# control_block.net
KiCad netlist of a schematic drawn in Altium Designer
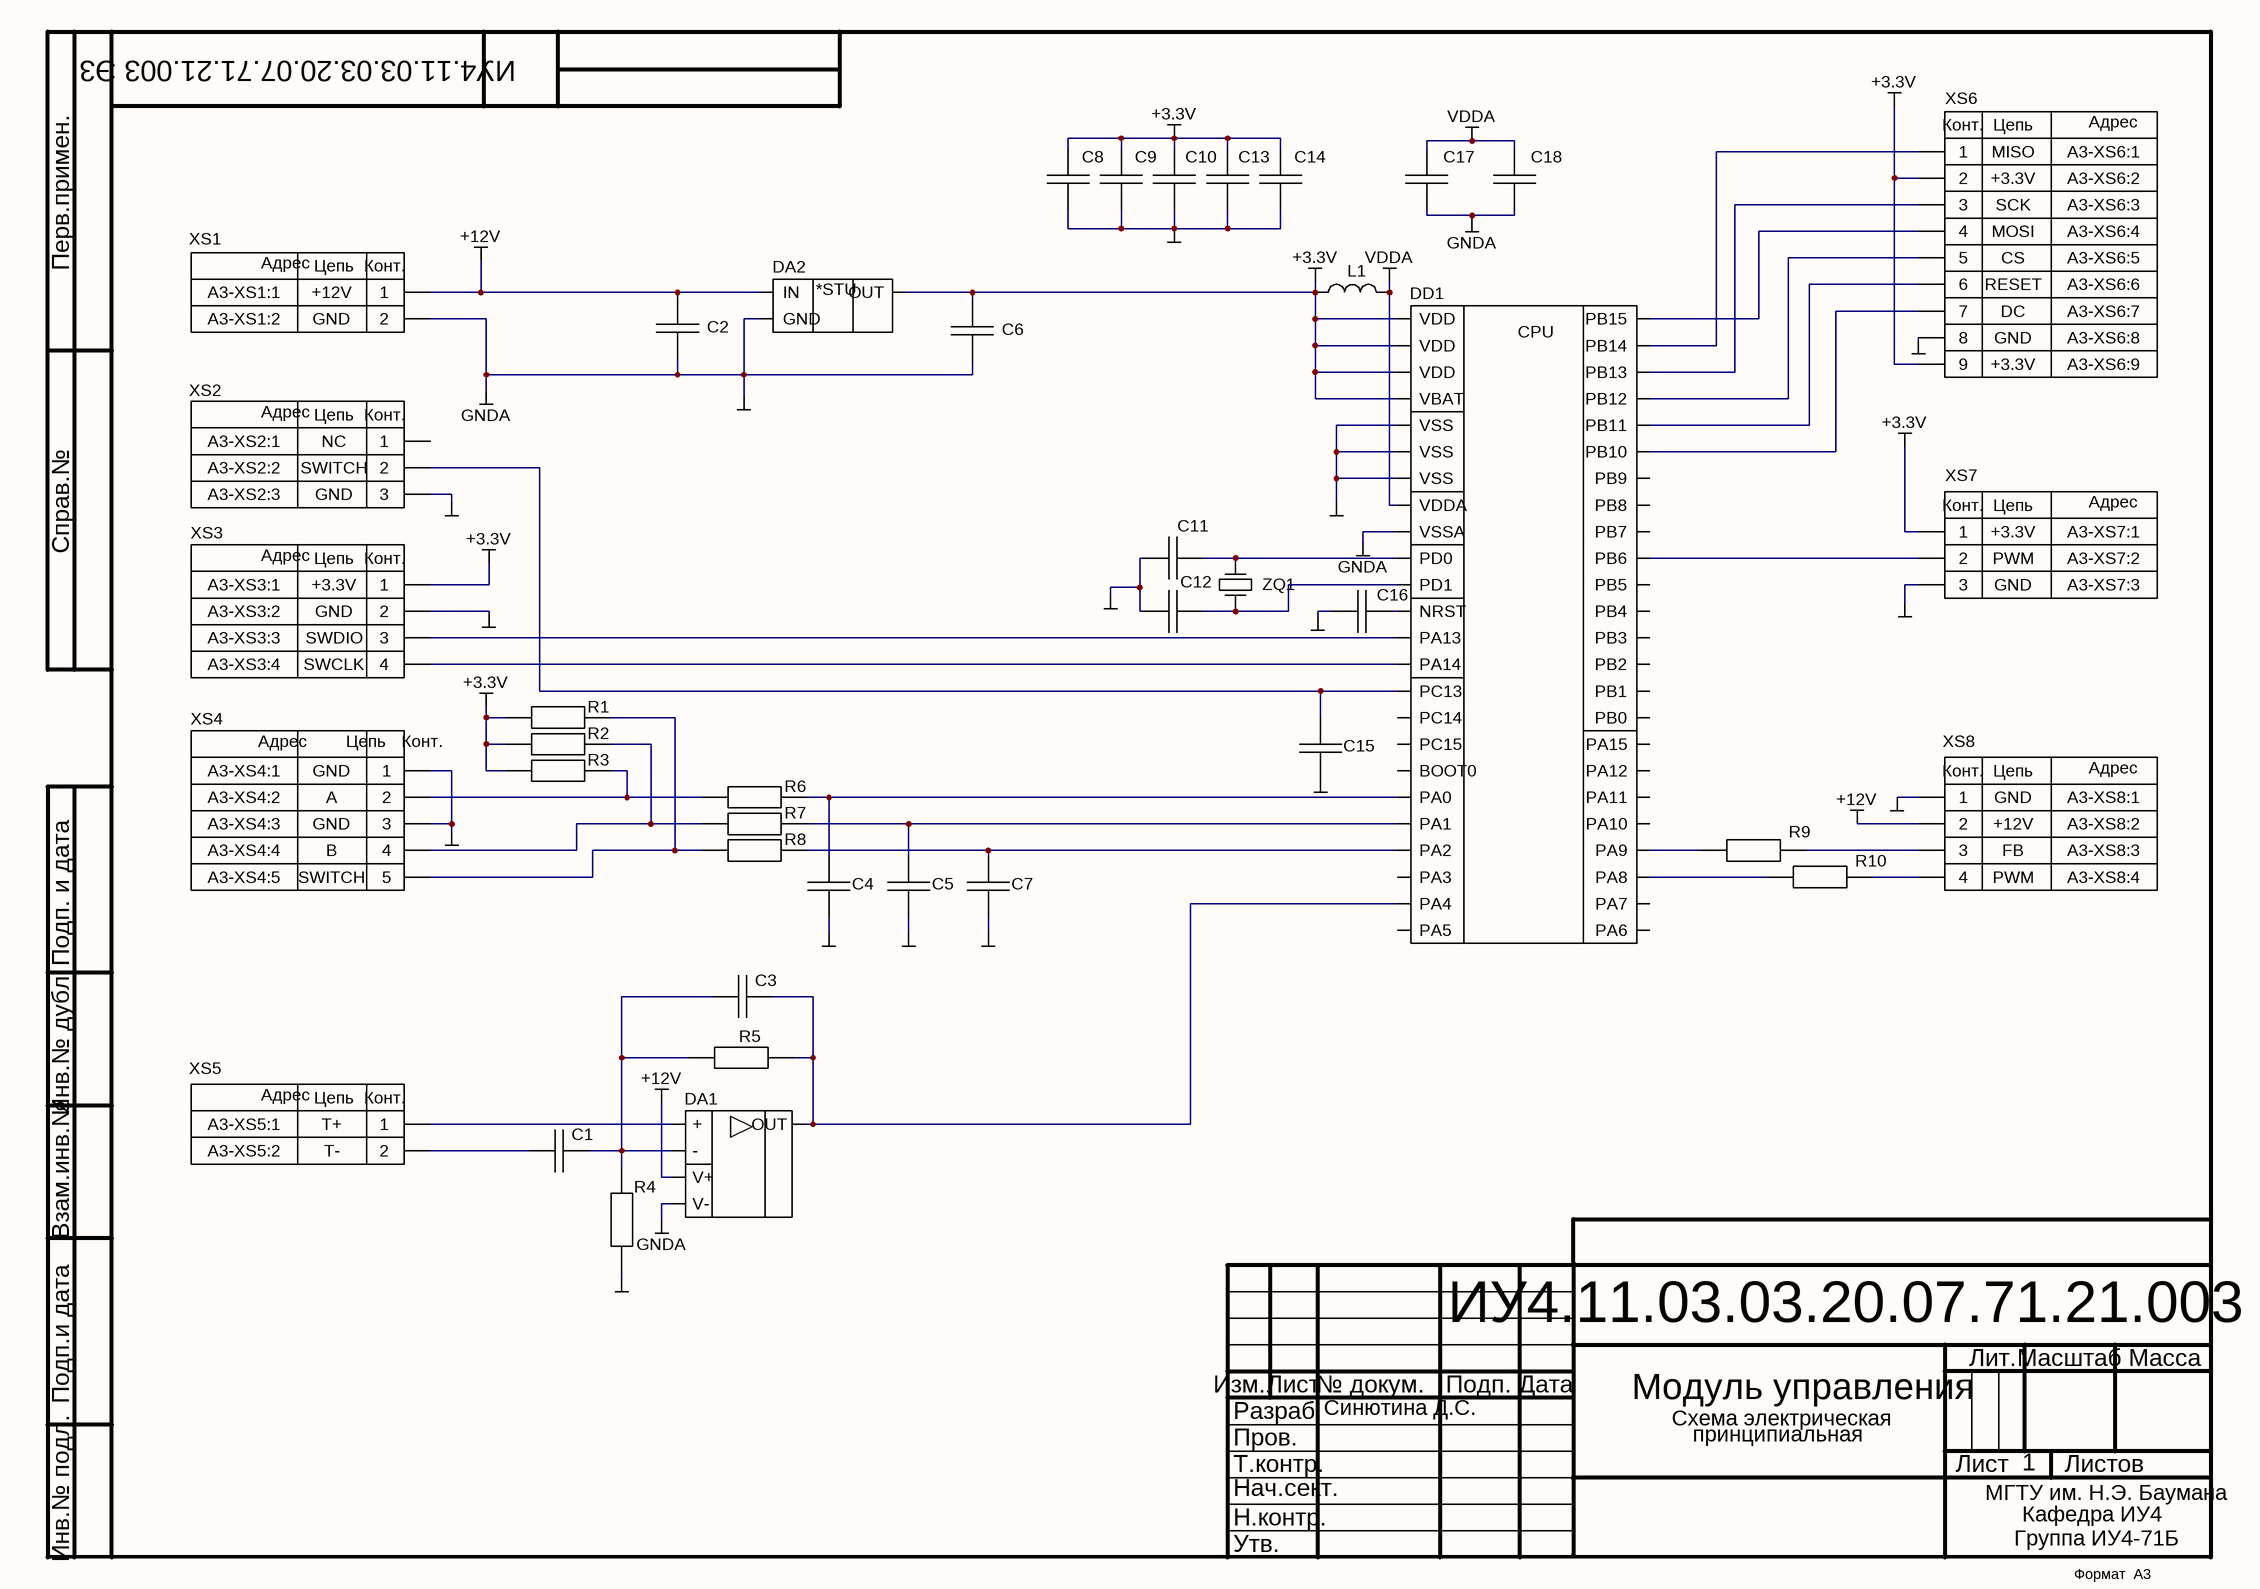
[diagram p0: control_block.SchDoc]

(export (version "E")
  (design (tool "Eeschema 10.0.6"))
  (components
    (comp (ref "C1") (value "100 нФ") (footprint "CAP: 0603") (libsource (lib "elems") (part "C_const")))
    (comp (ref "C2") (value "330 нФ") (footprint "CAP: 0603") (libsource (lib "elems") (part "C_const")))
    (comp (ref "C3") (value "100 нФ") (footprint "CAP: 0603") (libsource (lib "elems") (part "C_const")))
    (comp (ref "C4") (value "100 нФ") (footprint "CAP: 0603") (libsource (lib "elems") (part "C_const")))
    (comp (ref "C5") (value "100 нФ") (footprint "CAP: 0603") (libsource (lib "elems") (part "C_const")))
    (comp (ref "C6") (value "100 нФ") (footprint "CAP: 0603") (libsource (lib "elems") (part "C_const")))
    (comp (ref "C7") (value "100 нФ") (footprint "CAP: 0603") (libsource (lib "elems") (part "C_const")))
    (comp (ref "C8") (value "100 нФ") (footprint "CAP: 0603") (libsource (lib "elems") (part "C_const")))
    (comp (ref "C9") (value "100 нФ") (footprint "CAP: 0603") (libsource (lib "elems") (part "C_const")))
    (comp (ref "C10") (value "100 нФ") (footprint "CAP: 0603") (libsource (lib "elems") (part "C_const")))
    (comp (ref "C11") (value "22 pF") (footprint "CAP: 0603") (libsource (lib "elems") (part "C_const")))
    (comp (ref "C12") (value "22 pF") (footprint "CAP: 0603") (libsource (lib "elems") (part "C_const")))
    (comp (ref "C13") (value "100 нФ") (footprint "CAP: 0603") (libsource (lib "elems") (part "C_const")))
    (comp (ref "C14") (value "4.7 мкФ") (footprint "CAP: 0603") (libsource (lib "elems") (part "C_const")))
    (comp (ref "C15") (value "100 нФ") (footprint "CAP: 0603") (libsource (lib "") (part "C_const_2")))
    (comp (ref "C16") (value "100 нФ") (footprint "CAP: 0603") (libsource (lib "") (part "C_const_1")))
    (comp (ref "C17") (value "10 нФ") (footprint "CAP: 0603") (libsource (lib "elems") (part "C_const")))
    (comp (ref "C18") (value "1 мкФ") (footprint "CAP: 0603") (libsource (lib "elems") (part "C_const")))
    (comp (ref "DA1")
      (value "TS321ILT")
      (footprint "SOT23-5")
      (libsource (lib "elems") (part "single_channel_op_amp"))
    )
    (comp (ref "DA2") (value "78xx") (footprint "SOT89") (libsource (lib "elems") (part "78xx")))
    (comp (ref "DD1")
      (value "STM32F103C8T6")
      (footprint "48-LQFP")
      (libsource (lib "elems") (part "STM32F103C8T6"))
    )
    (comp (ref "L1") (value "10 мкГн") (footprint "IND: 0805") (libsource (lib "elems") (part "L")))
    (comp (ref "R1") (value "10кОм") (footprint "RES: 0603") (libsource (lib "elems") (part "Res")))
    (comp (ref "R2") (value "10кОм") (footprint "RES: 0603") (libsource (lib "elems") (part "Res")))
    (comp (ref "R3") (value "10кОм") (footprint "RES: 0603") (libsource (lib "elems") (part "Res")))
    (comp (ref "R4") (value "1 кОм") (footprint "RES: 1206") (libsource (lib "elems") (part "Res")))
    (comp (ref "R5") (value "47 кОм") (footprint "RES: 1206") (libsource (lib "elems") (part "Res")))
    (comp (ref "R6") (value "10кОм") (footprint "RES: 0603") (libsource (lib "elems") (part "Res")))
    (comp (ref "R7") (value "10кОм") (footprint "RES: 0603") (libsource (lib "elems") (part "Res")))
    (comp (ref "R8") (value "10кОм") (footprint "RES: 0603") (libsource (lib "elems") (part "Res")))
    (comp (ref "R9") (value "220 Ом") (footprint "RES: 1206") (libsource (lib "elems") (part "Res")))
    (comp (ref "R10") (value "220 Ом") (footprint "RES: 1206") (libsource (lib "elems") (part "Res")))
    (comp (ref "XS1")
      (value "X2")
      (footprint "CON: WF-02")
      (fields
        (field (name "CIRCUIT2") "GND")
        (field (name "CIRCUIT1") "+12V")
        (field (name "=ADDRESS2") "A3-XS1:2")
        (field (name "=ADDRESS1") "A3-XS1:1")
      )
      (libsource (lib "elems") (part "X2"))
    )
    (comp (ref "XS2")
      (value "X3")
      (footprint "CON: WF-03")
      (fields
        (field (name "CIRCUIT1") "NC")
        (field (name "CIRCUIT2") "SWITCH")
        (field (name "CIRCUIT3") "GND")
        (field (name "=ADDRESS1") "A3-XS2:1")
        (field (name "=ADDRESS2") "A3-XS2:2")
        (field (name "=ADDRESS3") "A3-XS2:3")
      )
      (libsource (lib "elems") (part "X3"))
    )
    (comp (ref "XS3")
      (value "X4")
      (footprint "CON: WF-04")
      (fields
        (field (name "CIRCUIT2") "GND")
        (field (name "CIRCUIT3") "SWDIO")
        (field (name "CIRCUIT1") "+3.3V")
        (field (name "CIRCUIT4") "SWCLK")
        (field (name "=ADDRESS4") "A3-XS3:4")
        (field (name "=ADDRESS3") "A3-XS3:3")
        (field (name "=ADDRESS2") "A3-XS3:2")
        (field (name "=ADDRESS1") "A3-XS3:1")
      )
      (libsource (lib "elems") (part "X4"))
    )
    (comp (ref "XS4")
      (value "X5")
      (footprint "CON: CWF-5")
      (fields
        (field (name "CIRTUIT5") "SWITCH")
        (field (name "CIRCUIT4") "B")
        (field (name "CIRCUIT3") "GND")
        (field (name "CIRCUIT2") "A")
        (field (name "CIRCUIT1") "GND")
        (field (name "=ADDRESS5") "A3-XS4:5")
        (field (name "=ADDRESS4") "A3-XS4:4")
        (field (name "=ADDRESS3") "A3-XS4:3")
        (field (name "=ADDRESS2") "A3-XS4:2")
        (field (name "=ADDRESS1") "A3-XS4:1")
      )
      (libsource (lib "elems") (part "X5"))
    )
    (comp (ref "XS5")
      (value "X2")
      (footprint "CON: WF-02")
      (fields
        (field (name "CIRCUIT2") "T-")
        (field (name "CIRCUIT1") "T+")
        (field (name "=ADDRESS2") "A3-XS5:2")
        (field (name "=ADDRESS1") "A3-XS5:1")
      )
      (libsource (lib "") (part "X2_1"))
    )
    (comp (ref "XS6")
      (value "X9")
      (footprint "CON: IDC-10MS")
      (fields
        (field (name "CIRCTUIT9") "+3.3V")
        (field (name "CIRCTUIT8") "GND")
        (field (name "CIRCTUIT7") "DC")
        (field (name "CIRCTUIT6") "RESET")
        (field (name "CIRCTUIT5") "CS")
        (field (name "CIRCTUIT4") "MOSI")
        (field (name "CIRCTUIT3") "SCK")
        (field (name "CIRCTUIT2") "+3.3V")
        (field (name "CIRCTUIT1") "MISO")
        (field (name "=ADDRESS9") "A3-XS6:9")
        (field (name "=ADDRESS8") "A3-XS6:8")
        (field (name "=ADDRESS7") "A3-XS6:7")
        (field (name "=ADDRESS5") "A3-XS6:5")
        (field (name "=ADDRESS6") "A3-XS6:6")
        (field (name "=ADDRESS4") "A3-XS6:4")
        (field (name "=ADDRESS3") "A3-XS6:3")
        (field (name "=ADDRESS2") "A3-XS6:2")
        (field (name "=ADDRESS1") "A3-XS6:1")
      )
      (libsource (lib "elems") (part "X9"))
    )
    (comp (ref "XS7")
      (value "X3")
      (footprint "CON: WF-03")
      (fields
        (field (name "CIRCUIT1") "+3.3V")
        (field (name "CIRCUIT2") "PWM")
        (field (name "CIRCUIT3") "GND")
        (field (name "=ADDRESS1") "A3-XS7:1")
        (field (name "=ADDRESS2") "A3-XS7:2")
        (field (name "=ADDRESS3") "A3-XS7:3")
      )
      (libsource (lib "elems") (part "X3"))
    )
    (comp (ref "XS8")
      (value "X4")
      (footprint "CON: WF-04")
      (fields
        (field (name "CIRCUIT2") "+12V")
        (field (name "CIRCUIT3") "FB")
        (field (name "CIRCUIT1") "GND")
        (field (name "CIRCUIT4") "PWM")
        (field (name "=ADDRESS4") "A3-XS8:4")
        (field (name "=ADDRESS3") "A3-XS8:3")
        (field (name "=ADDRESS2") "A3-XS8:2")
        (field (name "=ADDRESS1") "A3-XS8:1")
      )
      (libsource (lib "elems") (part "X4"))
    )
    (comp (ref "ZQ1") (value "AT-41CD2-8MHz") (footprint "AT-41CD2") (libsource (lib "elems") (part "ZQ")))
  )
  (nets
    (net (code "1") (name "+3.3V") (class "Default")
      (node (ref "C10") (pin "2") (pinfunction "2_2") (pintype "passive"))
      (node (ref "C13") (pin "2") (pinfunction "2_2") (pintype "passive"))
      (node (ref "C14") (pin "2") (pinfunction "2_2") (pintype "passive"))
      (node (ref "C6") (pin "2") (pinfunction "2_2") (pintype "passive"))
      (node (ref "C8") (pin "2") (pinfunction "2_2") (pintype "passive"))
      (node (ref "C9") (pin "2") (pinfunction "2_2") (pintype "passive"))
      (node (ref "DA2") (pin "2") (pinfunction "OUT_2") (pintype "passive"))
      (node (ref "DD1") (pin "1") (pinfunction "VBAT_1") (pintype "passive"))
      (node (ref "DD1") (pin "24") (pinfunction "VDD_24") (pintype "passive"))
      (node (ref "DD1") (pin "36") (pinfunction "VDD_36") (pintype "passive"))
      (node (ref "DD1") (pin "48") (pinfunction "VDD_48") (pintype "passive"))
      (node (ref "L1") (pin "1") (pinfunction "1_1") (pintype "passive"))
      (node (ref "R1") (pin "2") (pinfunction "6_2") (pintype "passive"))
      (node (ref "R2") (pin "2") (pinfunction "6_2") (pintype "passive"))
      (node (ref "R3") (pin "2") (pinfunction "6_2") (pintype "passive"))
      (node (ref "XS3") (pin "1") (pinfunction "1_1") (pintype "passive"))
      (node (ref "XS6") (pin "2") (pinfunction "2_2") (pintype "passive"))
      (node (ref "XS6") (pin "9") (pinfunction "9_9") (pintype "passive"))
      (node (ref "XS7") (pin "1") (pinfunction "1_1") (pintype "passive"))
    )
    (net (code "2") (name "+12V") (class "Default")
      (node (ref "C2") (pin "2") (pinfunction "2_2") (pintype "passive"))
      (node (ref "DA1") (pin "5") (pinfunction "V+_5") (pintype "passive"))
      (node (ref "DA2") (pin "1") (pinfunction "IN_1") (pintype "passive"))
      (node (ref "XS1") (pin "1") (pinfunction "1_1") (pintype "passive"))
      (node (ref "XS8") (pin "2") (pinfunction "2_2") (pintype "passive"))
    )
    (net (code "3") (name "GND") (class "Default")
      (node (ref "C10") (pin "1") (pinfunction "1_1") (pintype "passive"))
      (node (ref "C11") (pin "1") (pinfunction "1_1") (pintype "passive"))
      (node (ref "C12") (pin "1") (pinfunction "1_1") (pintype "passive"))
      (node (ref "C13") (pin "1") (pinfunction "1_1") (pintype "passive"))
      (node (ref "C14") (pin "1") (pinfunction "1_1") (pintype "passive"))
      (node (ref "C15") (pin "1") (pinfunction "1_1") (pintype "passive"))
      (node (ref "C16") (pin "1") (pinfunction "1_1") (pintype "passive"))
      (node (ref "C17") (pin "1") (pinfunction "1_1") (pintype "passive"))
      (node (ref "C18") (pin "1") (pinfunction "1_1") (pintype "passive"))
      (node (ref "C2") (pin "1") (pinfunction "1_1") (pintype "passive"))
      (node (ref "C4") (pin "1") (pinfunction "1_1") (pintype "passive"))
      (node (ref "C5") (pin "1") (pinfunction "1_1") (pintype "passive"))
      (node (ref "C6") (pin "1") (pinfunction "1_1") (pintype "passive"))
      (node (ref "C7") (pin "1") (pinfunction "1_1") (pintype "passive"))
      (node (ref "C8") (pin "1") (pinfunction "1_1") (pintype "passive"))
      (node (ref "C9") (pin "1") (pinfunction "1_1") (pintype "passive"))
      (node (ref "DA1") (pin "2") (pinfunction "V-_2") (pintype "passive"))
      (node (ref "DA2") (pin "3") (pinfunction "GND_3") (pintype "passive"))
      (node (ref "DD1") (pin "23") (pinfunction "VSS_23") (pintype "passive"))
      (node (ref "DD1") (pin "35") (pinfunction "VSS_35") (pintype "passive"))
      (node (ref "DD1") (pin "47") (pinfunction "VSS_47") (pintype "passive"))
      (node (ref "DD1") (pin "8") (pinfunction "VSSA_8") (pintype "passive"))
      (node (ref "R4") (pin "2") (pinfunction "6_2") (pintype "passive"))
      (node (ref "XS1") (pin "2") (pinfunction "2_2") (pintype "passive"))
      (node (ref "XS2") (pin "3") (pinfunction "3_3") (pintype "passive"))
      (node (ref "XS3") (pin "2") (pinfunction "2_2") (pintype "passive"))
      (node (ref "XS4") (pin "1") (pinfunction "1_1") (pintype "passive"))
      (node (ref "XS4") (pin "3") (pinfunction "3_3") (pintype "passive"))
      (node (ref "XS6") (pin "8") (pinfunction "8_8") (pintype "passive"))
      (node (ref "XS7") (pin "3") (pinfunction "3_3") (pintype "passive"))
      (node (ref "XS8") (pin "1") (pinfunction "1_1") (pintype "passive"))
    )
    (net (code "4") (name "Net-(C1-Pad1)") (class "Default")
      (node (ref "C1") (pin "1") (pinfunction "1_1") (pintype "passive"))
      (node (ref "XS5") (pin "2") (pinfunction "2_2") (pintype "passive"))
    )
    (net (code "5") (name "Net-(DA1-+)") (class "Default")
      (node (ref "DA1") (pin "1") (pinfunction "+_1") (pintype "passive"))
      (node (ref "XS5") (pin "1") (pinfunction "1_1") (pintype "passive"))
    )
    (net (code "6") (name "Net-(DA1--)") (class "Default")
      (node (ref "C1") (pin "2") (pinfunction "2_2") (pintype "passive"))
      (node (ref "C3") (pin "1") (pinfunction "1_1") (pintype "passive"))
      (node (ref "DA1") (pin "3") (pinfunction "-_3") (pintype "passive"))
      (node (ref "R4") (pin "1") (pinfunction "1_1") (pintype "passive"))
      (node (ref "R5") (pin "1") (pinfunction "1_1") (pintype "passive"))
    )
    (net (code "7") (name "Net-(DA1-OUT)") (class "Default")
      (node (ref "C3") (pin "2") (pinfunction "2_2") (pintype "passive"))
      (node (ref "DA1") (pin "4") (pinfunction "OUT_4") (pintype "passive"))
      (node (ref "DD1") (pin "14") (pinfunction "PA4_14") (pintype "passive"))
      (node (ref "R5") (pin "2") (pinfunction "6_2") (pintype "passive"))
    )
    (net (code "8") (name "Net-(DD1-NRST)") (class "Default")
      (node (ref "C16") (pin "2") (pinfunction "2_2") (pintype "passive"))
      (node (ref "DD1") (pin "7") (pinfunction "NRST_7") (pintype "passive"))
    )
    (net (code "9") (name "Net-(DD1-PA0)") (class "Default")
      (node (ref "C4") (pin "2") (pinfunction "2_2") (pintype "passive"))
      (node (ref "DD1") (pin "10") (pinfunction "PA0_10") (pintype "passive"))
      (node (ref "R6") (pin "2") (pinfunction "6_2") (pintype "passive"))
    )
    (net (code "10") (name "Net-(DD1-PA1)") (class "Default")
      (node (ref "C5") (pin "2") (pinfunction "2_2") (pintype "passive"))
      (node (ref "DD1") (pin "11") (pinfunction "PA1_11") (pintype "passive"))
      (node (ref "R7") (pin "2") (pinfunction "6_2") (pintype "passive"))
    )
    (net (code "11") (name "Net-(DD1-PA2)") (class "Default")
      (node (ref "C7") (pin "2") (pinfunction "2_2") (pintype "passive"))
      (node (ref "DD1") (pin "12") (pinfunction "PA2_12") (pintype "passive"))
      (node (ref "R8") (pin "2") (pinfunction "6_2") (pintype "passive"))
    )
    (net (code "12") (name "Net-(DD1-PA8)") (class "Default")
      (node (ref "DD1") (pin "29") (pinfunction "PA8_29") (pintype "passive"))
      (node (ref "R10") (pin "1") (pinfunction "1_1") (pintype "passive"))
    )
    (net (code "13") (name "Net-(DD1-PA9)") (class "Default")
      (node (ref "DD1") (pin "30") (pinfunction "PA9_30") (pintype "passive"))
      (node (ref "R9") (pin "1") (pinfunction "1_1") (pintype "passive"))
    )
    (net (code "14") (name "Net-(DD1-PA13)") (class "Default")
      (node (ref "DD1") (pin "34") (pinfunction "PA13_34") (pintype "passive"))
      (node (ref "XS3") (pin "3") (pinfunction "3_3") (pintype "passive"))
    )
    (net (code "15") (name "Net-(DD1-PA14)") (class "Default")
      (node (ref "DD1") (pin "37") (pinfunction "PA14_37") (pintype "passive"))
      (node (ref "XS3") (pin "4") (pinfunction "4_4") (pintype "passive"))
    )
    (net (code "16") (name "Net-(DD1-PB6)") (class "Default")
      (node (ref "DD1") (pin "42") (pinfunction "PB6_42") (pintype "passive"))
      (node (ref "XS7") (pin "2") (pinfunction "2_2") (pintype "passive"))
    )
    (net (code "17") (name "Net-(DD1-PB10)") (class "Default")
      (node (ref "DD1") (pin "21") (pinfunction "PB10_21") (pintype "passive"))
      (node (ref "XS6") (pin "7") (pinfunction "7_7") (pintype "passive"))
    )
    (net (code "18") (name "Net-(DD1-PB11)") (class "Default")
      (node (ref "DD1") (pin "22") (pinfunction "PB11_22") (pintype "passive"))
      (node (ref "XS6") (pin "6") (pinfunction "6_6") (pintype "passive"))
    )
    (net (code "19") (name "Net-(DD1-PB12)") (class "Default")
      (node (ref "DD1") (pin "25") (pinfunction "PB12_25") (pintype "passive"))
      (node (ref "XS6") (pin "5") (pinfunction "5_5") (pintype "passive"))
    )
    (net (code "20") (name "Net-(DD1-PB13)") (class "Default")
      (node (ref "DD1") (pin "26") (pinfunction "PB13_26") (pintype "passive"))
      (node (ref "XS6") (pin "3") (pinfunction "3_3") (pintype "passive"))
    )
    (net (code "21") (name "Net-(DD1-PB14)") (class "Default")
      (node (ref "DD1") (pin "27") (pinfunction "PB14_27") (pintype "passive"))
      (node (ref "XS6") (pin "1") (pinfunction "1_1") (pintype "passive"))
    )
    (net (code "22") (name "Net-(DD1-PB15)") (class "Default")
      (node (ref "DD1") (pin "28") (pinfunction "PB15_28") (pintype "passive"))
      (node (ref "XS6") (pin "4") (pinfunction "4_4") (pintype "passive"))
    )
    (net (code "23") (name "Net-(DD1-PC13)") (class "Default")
      (node (ref "C15") (pin "2") (pinfunction "2_2") (pintype "passive"))
      (node (ref "DD1") (pin "2") (pinfunction "PC13_2") (pintype "passive"))
      (node (ref "XS2") (pin "2") (pinfunction "2_2") (pintype "passive"))
    )
    (net (code "24") (name "Net-(DD1-PD0)") (class "Default")
      (node (ref "C11") (pin "2") (pinfunction "2_2") (pintype "passive"))
      (node (ref "DD1") (pin "5") (pinfunction "PD0_5") (pintype "passive"))
      (node (ref "ZQ1") (pin "1") (pinfunction "1_1") (pintype "passive"))
    )
    (net (code "25") (name "Net-(DD1-PD1)") (class "Default")
      (node (ref "C12") (pin "2") (pinfunction "2_2") (pintype "passive"))
      (node (ref "DD1") (pin "6") (pinfunction "PD1_6") (pintype "passive"))
      (node (ref "ZQ1") (pin "2") (pinfunction "2_2") (pintype "passive"))
    )
    (net (code "26") (name "Net-(R1-Pad1)") (class "Default")
      (node (ref "R1") (pin "1") (pinfunction "1_1") (pintype "passive"))
      (node (ref "R8") (pin "1") (pinfunction "1_1") (pintype "passive"))
      (node (ref "XS4") (pin "5") (pinfunction "5_5") (pintype "passive"))
    )
    (net (code "27") (name "Net-(R2-Pad1)") (class "Default")
      (node (ref "R2") (pin "1") (pinfunction "1_1") (pintype "passive"))
      (node (ref "R7") (pin "1") (pinfunction "1_1") (pintype "passive"))
      (node (ref "XS4") (pin "4") (pinfunction "4_4") (pintype "passive"))
    )
    (net (code "28") (name "Net-(R3-Pad1)") (class "Default")
      (node (ref "R3") (pin "1") (pinfunction "1_1") (pintype "passive"))
      (node (ref "R6") (pin "1") (pinfunction "1_1") (pintype "passive"))
      (node (ref "XS4") (pin "2") (pinfunction "2_2") (pintype "passive"))
    )
    (net (code "29") (name "Net-(R9-6)") (class "Default")
      (node (ref "R9") (pin "2") (pinfunction "6_2") (pintype "passive"))
      (node (ref "XS8") (pin "3") (pinfunction "3_3") (pintype "passive"))
    )
    (net (code "30") (name "Net-(R10-6)") (class "Default")
      (node (ref "R10") (pin "2") (pinfunction "6_2") (pintype "passive"))
      (node (ref "XS8") (pin "4") (pinfunction "4_4") (pintype "passive"))
    )
    (net (code "31") (name "VDDA") (class "Default")
      (node (ref "C17") (pin "2") (pinfunction "2_2") (pintype "passive"))
      (node (ref "C18") (pin "2") (pinfunction "2_2") (pintype "passive"))
      (node (ref "DD1") (pin "9") (pinfunction "VDDA_9") (pintype "passive"))
      (node (ref "L1") (pin "2") (pinfunction "2_2") (pintype "passive"))
    )
    (net (code "32") (name "unconnected-(DD1-BOOT0-Pad44)") (class "Default")
      (node (ref "DD1") (pin "44") (pinfunction "BOOT0_44") (pintype "passive"))
    )
    (net (code "33") (name "unconnected-(DD1-PA3-Pad13)") (class "Default")
      (node (ref "DD1") (pin "13") (pinfunction "PA3_13") (pintype "passive"))
    )
    (net (code "34") (name "unconnected-(DD1-PA5-Pad15)") (class "Default")
      (node (ref "DD1") (pin "15") (pinfunction "PA5_15") (pintype "passive"))
    )
    (net (code "35") (name "unconnected-(DD1-PA6-Pad16)") (class "Default")
      (node (ref "DD1") (pin "16") (pinfunction "PA6_16") (pintype "passive"))
    )
    (net (code "36") (name "unconnected-(DD1-PA7-Pad17)") (class "Default")
      (node (ref "DD1") (pin "17") (pinfunction "PA7_17") (pintype "passive"))
    )
    (net (code "37") (name "unconnected-(DD1-PA10-Pad31)") (class "Default")
      (node (ref "DD1") (pin "31") (pinfunction "PA10_31") (pintype "passive"))
    )
    (net (code "38") (name "unconnected-(DD1-PA11-Pad32)") (class "Default")
      (node (ref "DD1") (pin "32") (pinfunction "PA11_32") (pintype "passive"))
    )
    (net (code "39") (name "unconnected-(DD1-PA12-Pad33)") (class "Default")
      (node (ref "DD1") (pin "33") (pinfunction "PA12_33") (pintype "passive"))
    )
    (net (code "40") (name "unconnected-(DD1-PA15-Pad38)") (class "Default")
      (node (ref "DD1") (pin "38") (pinfunction "PA15_38") (pintype "passive"))
    )
    (net (code "41") (name "unconnected-(DD1-PB0-Pad18)") (class "Default")
      (node (ref "DD1") (pin "18") (pinfunction "PB0_18") (pintype "passive"))
    )
    (net (code "42") (name "unconnected-(DD1-PB1-Pad19)") (class "Default")
      (node (ref "DD1") (pin "19") (pinfunction "PB1_19") (pintype "passive"))
    )
    (net (code "43") (name "unconnected-(DD1-PB2-Pad20)") (class "Default")
      (node (ref "DD1") (pin "20") (pinfunction "PB2_20") (pintype "passive"))
    )
    (net (code "44") (name "unconnected-(DD1-PB3-Pad39)") (class "Default")
      (node (ref "DD1") (pin "39") (pinfunction "PB3_39") (pintype "passive"))
    )
    (net (code "45") (name "unconnected-(DD1-PB4-Pad40)") (class "Default")
      (node (ref "DD1") (pin "40") (pinfunction "PB4_40") (pintype "passive"))
    )
    (net (code "46") (name "unconnected-(DD1-PB5-Pad41)") (class "Default")
      (node (ref "DD1") (pin "41") (pinfunction "PB5_41") (pintype "passive"))
    )
    (net (code "47") (name "unconnected-(DD1-PB7-Pad43)") (class "Default")
      (node (ref "DD1") (pin "43") (pinfunction "PB7_43") (pintype "passive"))
    )
    (net (code "48") (name "unconnected-(DD1-PB8-Pad45)") (class "Default")
      (node (ref "DD1") (pin "45") (pinfunction "PB8_45") (pintype "passive"))
    )
    (net (code "49") (name "unconnected-(DD1-PB9-Pad46)") (class "Default")
      (node (ref "DD1") (pin "46") (pinfunction "PB9_46") (pintype "passive"))
    )
    (net (code "50") (name "unconnected-(DD1-PC14-Pad3)") (class "Default")
      (node (ref "DD1") (pin "3") (pinfunction "PC14_3") (pintype "passive"))
    )
    (net (code "51") (name "unconnected-(DD1-PC15-Pad4)") (class "Default")
      (node (ref "DD1") (pin "4") (pinfunction "PC15_4") (pintype "passive"))
    )
    (net (code "52") (name "unconnected-(XS2-Pad1)") (class "Default")
      (node (ref "XS2") (pin "1") (pinfunction "1_1") (pintype "passive"))
    )
  )
)
